# 18-Led7.net
KiCad netlist of a schematic drawn in Altium Designer
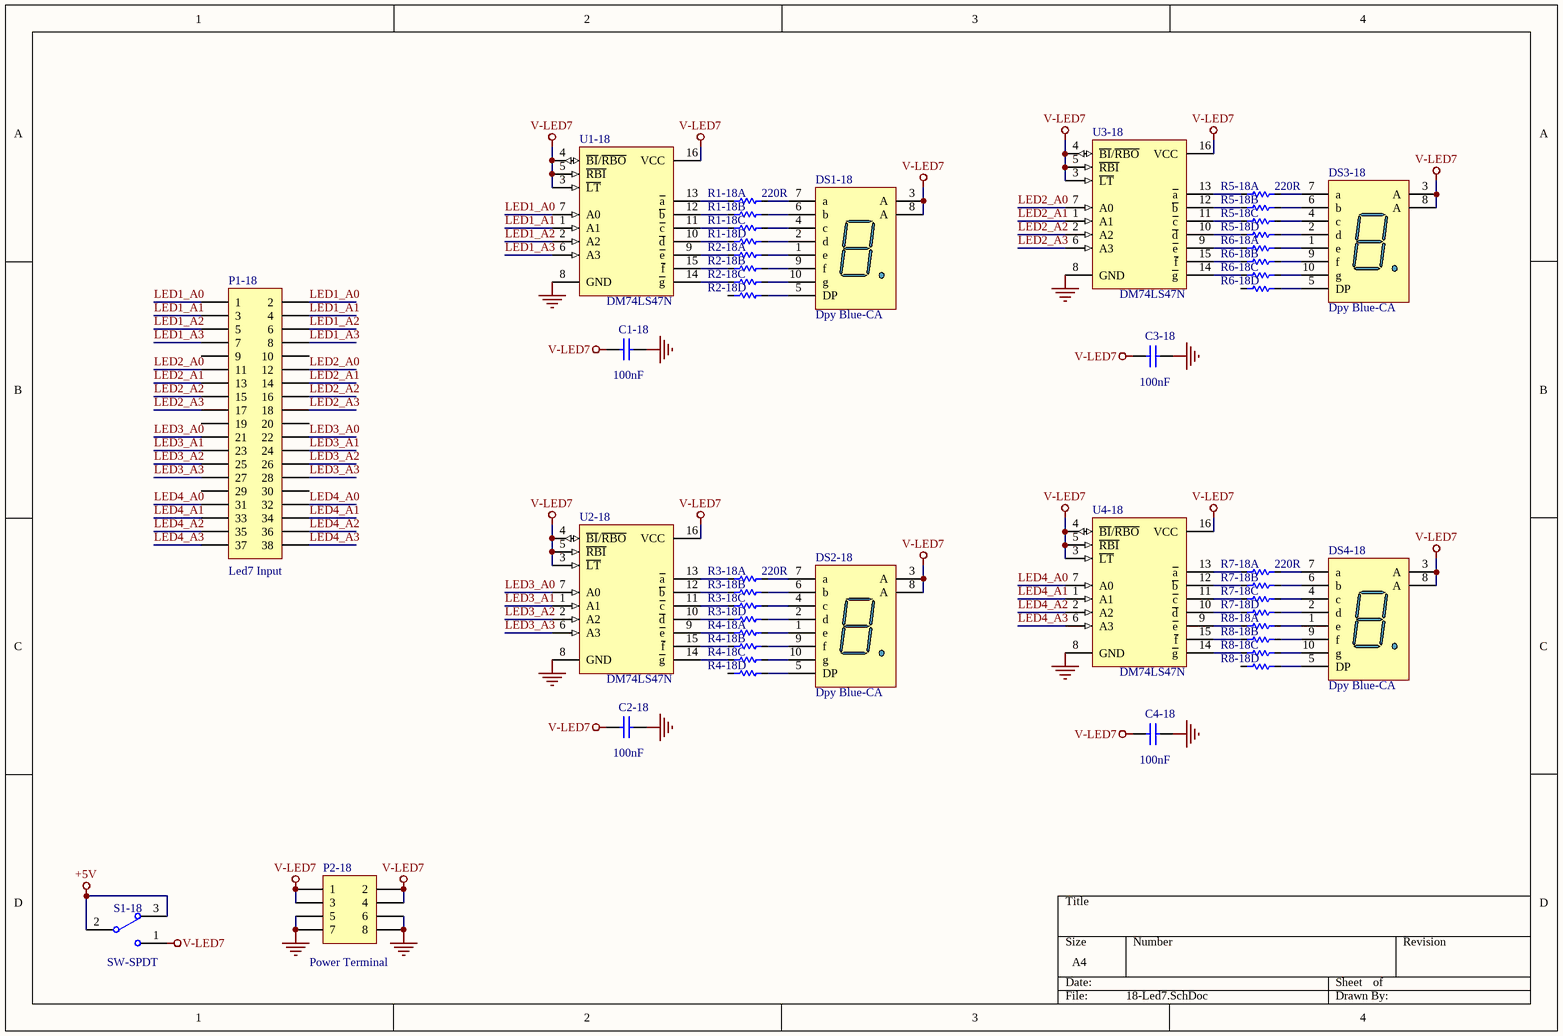
[diagram p0: 18-Led7.SchDoc]

(export (version "E")
  (design (tool "Eeschema 10.0.6"))
  (components
    (comp (ref "C1-18")
      (value "100nF")
      (footprint "c-0805")
      (description "Capacitor")
      (fields (field (name "Comment") "104") (field (name "PUBLISHER") "Altium Limited"))
      (libsource (lib "Miscellaneous Devices") (part "Cap"))
    )
    (comp (ref "C2-18")
      (value "100nF")
      (footprint "c-0805")
      (description "Capacitor")
      (fields (field (name "Comment") "104") (field (name "PUBLISHER") "Altium Limited"))
      (libsource (lib "Miscellaneous Devices") (part "Cap"))
    )
    (comp (ref "C3-18")
      (value "100nF")
      (footprint "c-0805")
      (description "Capacitor")
      (fields (field (name "Comment") "104") (field (name "PUBLISHER") "Altium Limited"))
      (libsource (lib "Miscellaneous Devices") (part "Cap"))
    )
    (comp (ref "C4-18")
      (value "100nF")
      (footprint "c-0805")
      (description "Capacitor")
      (fields (field (name "Comment") "104") (field (name "PUBLISHER") "Altium Limited"))
      (libsource (lib "Miscellaneous Devices") (part "Cap"))
    )
    (comp (ref "DS1-18")
      (value "Dpy Blue-CA")
      (footprint "LED7-0.56inch")
      (description "14.2 mm General Purpose Blue 7-Segment Display: CA, RH DP, Gray Surface")
      (fields (field (name "PUBLISHER") "Altium Limited"))
      (libsource (lib "Miscellaneous Devices") (part "Dpy Blue-CA"))
    )
    (comp (ref "DS2-18")
      (value "Dpy Blue-CA")
      (footprint "LED7-0.56inch")
      (description "14.2 mm General Purpose Blue 7-Segment Display: CA, RH DP, Gray Surface")
      (fields (field (name "PUBLISHER") "Altium Limited"))
      (libsource (lib "Miscellaneous Devices") (part "Dpy Blue-CA"))
    )
    (comp (ref "DS3-18")
      (value "Dpy Blue-CA")
      (footprint "LED7-0.56inch")
      (description "14.2 mm General Purpose Blue 7-Segment Display: CA, RH DP, Gray Surface")
      (fields (field (name "PUBLISHER") "Altium Limited"))
      (libsource (lib "Miscellaneous Devices") (part "Dpy Blue-CA"))
    )
    (comp (ref "DS4-18")
      (value "Dpy Blue-CA")
      (footprint "LED7-0.56inch")
      (description "14.2 mm General Purpose Blue 7-Segment Display: CA, RH DP, Gray Surface")
      (fields (field (name "PUBLISHER") "Altium Limited"))
      (libsource (lib "Miscellaneous Devices") (part "Dpy Blue-CA"))
    )
    (comp (ref "P1-18")
      (value "Led7 Input")
      (footprint "JP2.54-F-2x19A")
      (description "Header, 19-Pin, Dual row")
      (fields (field (name "Comment") "Header 19X2"))
      (libsource (lib "Miscellaneous Connectors") (part "Header 19X2"))
    )
    (comp (ref "P2-18")
      (value "Header 4X2")
      (footprint "JP2.54-F-2x04A")
      (description "Header, 4-Pin, Dual row")
      (fields (field (name "PUBLISHER") "Power Terminal"))
      (libsource (lib "Miscellaneous Connectors") (part "Header 4X2"))
    )
    (comp (ref "R1-18")
      (value "220R")
      (footprint "R-Array-0603-4")
      (description "RES ARRAY 4 RES 330 OHM 1206")
      (fields
        (field (name "DIGI-KEY PART NUMBER") "Y9331TR-ND")
        (field (name "MANUFACTURER") "Panasonic Electronic Components")
      )
      (libsource (lib "Dlib") (part "R-8P4R"))
    )
    (comp (ref "R2-18")
      (value "220R")
      (footprint "R-Array-0603-4")
      (description "RES ARRAY 4 RES 330 OHM 1206")
      (fields
        (field (name "DIGI-KEY PART NUMBER") "Y9331TR-ND")
        (field (name "MANUFACTURER") "Panasonic Electronic Components")
      )
      (libsource (lib "Dlib") (part "R-8P4R"))
    )
    (comp (ref "R3-18")
      (value "220R")
      (footprint "R-Array-0603-4")
      (description "RES ARRAY 4 RES 330 OHM 1206")
      (fields
        (field (name "DIGI-KEY PART NUMBER") "Y9331TR-ND")
        (field (name "MANUFACTURER") "Panasonic Electronic Components")
      )
      (libsource (lib "Dlib") (part "R-8P4R"))
    )
    (comp (ref "R4-18")
      (value "220R")
      (footprint "R-Array-0603-4")
      (description "RES ARRAY 4 RES 330 OHM 1206")
      (fields
        (field (name "DIGI-KEY PART NUMBER") "Y9331TR-ND")
        (field (name "MANUFACTURER") "Panasonic Electronic Components")
      )
      (libsource (lib "Dlib") (part "R-8P4R"))
    )
    (comp (ref "R5-18")
      (value "220R")
      (footprint "R-Array-0603-4")
      (description "RES ARRAY 4 RES 330 OHM 1206")
      (fields
        (field (name "DIGI-KEY PART NUMBER") "Y9331TR-ND")
        (field (name "MANUFACTURER") "Panasonic Electronic Components")
      )
      (libsource (lib "Dlib") (part "R-8P4R"))
    )
    (comp (ref "R6-18")
      (value "220R")
      (footprint "R-Array-0603-4")
      (description "RES ARRAY 4 RES 330 OHM 1206")
      (fields
        (field (name "DIGI-KEY PART NUMBER") "Y9331TR-ND")
        (field (name "MANUFACTURER") "Panasonic Electronic Components")
      )
      (libsource (lib "Dlib") (part "R-8P4R"))
    )
    (comp (ref "R7-18")
      (value "220R")
      (footprint "R-Array-0603-4")
      (description "RES ARRAY 4 RES 330 OHM 1206")
      (fields
        (field (name "DIGI-KEY PART NUMBER") "Y9331TR-ND")
        (field (name "MANUFACTURER") "Panasonic Electronic Components")
      )
      (libsource (lib "Dlib") (part "R-8P4R"))
    )
    (comp (ref "R8-18")
      (value "220R")
      (footprint "R-Array-0603-4")
      (description "RES ARRAY 4 RES 330 OHM 1206")
      (fields
        (field (name "DIGI-KEY PART NUMBER") "Y9331TR-ND")
        (field (name "MANUFACTURER") "Panasonic Electronic Components")
      )
      (libsource (lib "Dlib") (part "R-8P4R"))
    )
    (comp (ref "S1-18")
      (value "SW-SPDT")
      (footprint "SW-SLIDE-2P-2W")
      (description "SPDT Subminiature Toggle Switch, Right Angle Mounting, Vertical Actuation")
      (fields (field (name "PUBLISHER") "Altium Limited"))
      (libsource (lib "Miscellaneous Devices") (part "SW-SPDT"))
    )
    (comp (ref "U1-18")
      (value "DM74LS47N")
      (footprint "SK-DIP16-300")
      (description "BCD to 7-Segment Decoder/Driver with Open-Collector Output")
      (fields (field (name "PUBLISHER") "Altium Limited"))
      (libsource (lib "FSC Interface Display Driver") (part "DM74LS47N"))
    )
    (comp (ref "U2-18")
      (value "DM74LS47N")
      (footprint "SK-DIP16-300")
      (description "BCD to 7-Segment Decoder/Driver with Open-Collector Output")
      (fields (field (name "PUBLISHER") "Altium Limited"))
      (libsource (lib "FSC Interface Display Driver") (part "DM74LS47N"))
    )
    (comp (ref "U3-18")
      (value "DM74LS47N")
      (footprint "SK-DIP16-300")
      (description "BCD to 7-Segment Decoder/Driver with Open-Collector Output")
      (fields (field (name "PUBLISHER") "Altium Limited"))
      (libsource (lib "FSC Interface Display Driver") (part "DM74LS47N"))
    )
    (comp (ref "U4-18")
      (value "DM74LS47N")
      (footprint "SK-DIP16-300")
      (description "BCD to 7-Segment Decoder/Driver with Open-Collector Output")
      (fields (field (name "PUBLISHER") "Altium Limited"))
      (libsource (lib "FSC Interface Display Driver") (part "DM74LS47N"))
    )
  )
  (nets
    (net (code "1") (name "+5V") (class "Default")
      (node (ref "S1-18") (pin "2") (pinfunction "2_2") (pintype "passive"))
      (node (ref "S1-18") (pin "3") (pinfunction "3_3") (pintype "passive"))
    )
    (net (code "2") (name "/LED1_A0") (class "Default")
      (node (ref "P1-18") (pin "1") (pinfunction "1_1") (pintype "passive"))
      (node (ref "P1-18") (pin "2") (pinfunction "2_2") (pintype "passive"))
      (node (ref "U1-18") (pin "7") (pinfunction "A0_7") (pintype "input"))
    )
    (net (code "3") (name "/LED1_A1") (class "Default")
      (node (ref "P1-18") (pin "3") (pinfunction "3_3") (pintype "passive"))
      (node (ref "P1-18") (pin "4") (pinfunction "4_4") (pintype "passive"))
      (node (ref "U1-18") (pin "1") (pinfunction "A1_1") (pintype "input"))
    )
    (net (code "4") (name "/LED1_A2") (class "Default")
      (node (ref "P1-18") (pin "5") (pinfunction "5_5") (pintype "passive"))
      (node (ref "P1-18") (pin "6") (pinfunction "6_6") (pintype "passive"))
      (node (ref "U1-18") (pin "2") (pinfunction "A2_2") (pintype "input"))
    )
    (net (code "5") (name "/LED1_A3") (class "Default")
      (node (ref "P1-18") (pin "7") (pinfunction "7_7") (pintype "passive"))
      (node (ref "P1-18") (pin "8") (pinfunction "8_8") (pintype "passive"))
      (node (ref "U1-18") (pin "6") (pinfunction "A3_6") (pintype "input"))
    )
    (net (code "6") (name "/LED2_A0") (class "Default")
      (node (ref "P1-18") (pin "11") (pinfunction "11_11") (pintype "passive"))
      (node (ref "P1-18") (pin "12") (pinfunction "12_12") (pintype "passive"))
      (node (ref "U3-18") (pin "7") (pinfunction "A0_7") (pintype "input"))
    )
    (net (code "7") (name "/LED2_A1") (class "Default")
      (node (ref "P1-18") (pin "13") (pinfunction "13_13") (pintype "passive"))
      (node (ref "P1-18") (pin "14") (pinfunction "14_14") (pintype "passive"))
      (node (ref "U3-18") (pin "1") (pinfunction "A1_1") (pintype "input"))
    )
    (net (code "8") (name "/LED2_A2") (class "Default")
      (node (ref "P1-18") (pin "15") (pinfunction "15_15") (pintype "passive"))
      (node (ref "P1-18") (pin "16") (pinfunction "16_16") (pintype "passive"))
      (node (ref "U3-18") (pin "2") (pinfunction "A2_2") (pintype "input"))
    )
    (net (code "9") (name "/LED2_A3") (class "Default")
      (node (ref "P1-18") (pin "17") (pinfunction "17_17") (pintype "passive"))
      (node (ref "P1-18") (pin "18") (pinfunction "18_18") (pintype "passive"))
      (node (ref "U3-18") (pin "6") (pinfunction "A3_6") (pintype "input"))
    )
    (net (code "10") (name "/LED3_A0") (class "Default")
      (node (ref "P1-18") (pin "21") (pinfunction "21_21") (pintype "passive"))
      (node (ref "P1-18") (pin "22") (pinfunction "22_22") (pintype "passive"))
      (node (ref "U2-18") (pin "7") (pinfunction "A0_7") (pintype "input"))
    )
    (net (code "11") (name "/LED3_A1") (class "Default")
      (node (ref "P1-18") (pin "23") (pinfunction "23_23") (pintype "passive"))
      (node (ref "P1-18") (pin "24") (pinfunction "24_24") (pintype "passive"))
      (node (ref "U2-18") (pin "1") (pinfunction "A1_1") (pintype "input"))
    )
    (net (code "12") (name "/LED3_A2") (class "Default")
      (node (ref "P1-18") (pin "25") (pinfunction "25_25") (pintype "passive"))
      (node (ref "P1-18") (pin "26") (pinfunction "26_26") (pintype "passive"))
      (node (ref "U2-18") (pin "2") (pinfunction "A2_2") (pintype "input"))
    )
    (net (code "13") (name "/LED3_A3") (class "Default")
      (node (ref "P1-18") (pin "27") (pinfunction "27_27") (pintype "passive"))
      (node (ref "P1-18") (pin "28") (pinfunction "28_28") (pintype "passive"))
      (node (ref "U2-18") (pin "6") (pinfunction "A3_6") (pintype "input"))
    )
    (net (code "14") (name "/LED4_A0") (class "Default")
      (node (ref "P1-18") (pin "31") (pinfunction "31_31") (pintype "passive"))
      (node (ref "P1-18") (pin "32") (pinfunction "32_32") (pintype "passive"))
      (node (ref "U4-18") (pin "7") (pinfunction "A0_7") (pintype "input"))
    )
    (net (code "15") (name "/LED4_A1") (class "Default")
      (node (ref "P1-18") (pin "33") (pinfunction "33_33") (pintype "passive"))
      (node (ref "P1-18") (pin "34") (pinfunction "34_34") (pintype "passive"))
      (node (ref "U4-18") (pin "1") (pinfunction "A1_1") (pintype "input"))
    )
    (net (code "16") (name "/LED4_A2") (class "Default")
      (node (ref "P1-18") (pin "35") (pinfunction "35_35") (pintype "passive"))
      (node (ref "P1-18") (pin "36") (pinfunction "36_36") (pintype "passive"))
      (node (ref "U4-18") (pin "2") (pinfunction "A2_2") (pintype "input"))
    )
    (net (code "17") (name "/LED4_A3") (class "Default")
      (node (ref "P1-18") (pin "37") (pinfunction "37_37") (pintype "passive"))
      (node (ref "P1-18") (pin "38") (pinfunction "38_38") (pintype "passive"))
      (node (ref "U4-18") (pin "6") (pinfunction "A3_6") (pintype "input"))
    )
    (net (code "18") (name "GND") (class "Default")
      (node (ref "C1-18") (pin "2") (pinfunction "2_2") (pintype "passive"))
      (node (ref "C2-18") (pin "2") (pinfunction "2_2") (pintype "passive"))
      (node (ref "C3-18") (pin "2") (pinfunction "2_2") (pintype "passive"))
      (node (ref "C4-18") (pin "2") (pinfunction "2_2") (pintype "passive"))
      (node (ref "P2-18") (pin "5") (pinfunction "5_5") (pintype "passive"))
      (node (ref "P2-18") (pin "6") (pinfunction "6_6") (pintype "passive"))
      (node (ref "P2-18") (pin "7") (pinfunction "7_7") (pintype "passive"))
      (node (ref "P2-18") (pin "8") (pinfunction "8_8") (pintype "passive"))
      (node (ref "U1-18") (pin "8") (pinfunction "GND_8") (pintype "power_in"))
      (node (ref "U2-18") (pin "8") (pinfunction "GND_8") (pintype "power_in"))
      (node (ref "U3-18") (pin "8") (pinfunction "GND_8") (pintype "power_in"))
      (node (ref "U4-18") (pin "8") (pinfunction "GND_8") (pintype "power_in"))
    )
    (net (code "19") (name "Net-(DS1-18-DP)") (class "Default")
      (node (ref "DS1-18") (pin "5") (pinfunction "DP_5") (pintype "passive"))
      (node (ref "R2-18") (pin "8") (pinfunction "2_8") (pintype "passive"))
    )
    (net (code "20") (name "Net-(DS1-18-a)") (class "Default")
      (node (ref "DS1-18") (pin "7") (pinfunction "a_7") (pintype "passive"))
      (node (ref "R1-18") (pin "2") (pinfunction "2_2") (pintype "passive"))
    )
    (net (code "21") (name "Net-(DS1-18-b)") (class "Default")
      (node (ref "DS1-18") (pin "6") (pinfunction "b_6") (pintype "passive"))
      (node (ref "R1-18") (pin "4") (pinfunction "2_4") (pintype "passive"))
    )
    (net (code "22") (name "Net-(DS1-18-c)") (class "Default")
      (node (ref "DS1-18") (pin "4") (pinfunction "c_4") (pintype "passive"))
      (node (ref "R1-18") (pin "6") (pinfunction "2_6") (pintype "passive"))
    )
    (net (code "23") (name "Net-(DS1-18-d)") (class "Default")
      (node (ref "DS1-18") (pin "2") (pinfunction "d_2") (pintype "passive"))
      (node (ref "R1-18") (pin "8") (pinfunction "2_8") (pintype "passive"))
    )
    (net (code "24") (name "Net-(DS1-18-e)") (class "Default")
      (node (ref "DS1-18") (pin "1") (pinfunction "e_1") (pintype "passive"))
      (node (ref "R2-18") (pin "2") (pinfunction "2_2") (pintype "passive"))
    )
    (net (code "25") (name "Net-(DS1-18-f)") (class "Default")
      (node (ref "DS1-18") (pin "9") (pinfunction "f_9") (pintype "passive"))
      (node (ref "R2-18") (pin "4") (pinfunction "2_4") (pintype "passive"))
    )
    (net (code "26") (name "Net-(DS1-18-g)") (class "Default")
      (node (ref "DS1-18") (pin "10") (pinfunction "g_10") (pintype "passive"))
      (node (ref "R2-18") (pin "6") (pinfunction "2_6") (pintype "passive"))
    )
    (net (code "27") (name "Net-(DS2-18-DP)") (class "Default")
      (node (ref "DS2-18") (pin "5") (pinfunction "DP_5") (pintype "passive"))
      (node (ref "R4-18") (pin "8") (pinfunction "2_8") (pintype "passive"))
    )
    (net (code "28") (name "Net-(DS2-18-a)") (class "Default")
      (node (ref "DS2-18") (pin "7") (pinfunction "a_7") (pintype "passive"))
      (node (ref "R3-18") (pin "2") (pinfunction "2_2") (pintype "passive"))
    )
    (net (code "29") (name "Net-(DS2-18-b)") (class "Default")
      (node (ref "DS2-18") (pin "6") (pinfunction "b_6") (pintype "passive"))
      (node (ref "R3-18") (pin "4") (pinfunction "2_4") (pintype "passive"))
    )
    (net (code "30") (name "Net-(DS2-18-c)") (class "Default")
      (node (ref "DS2-18") (pin "4") (pinfunction "c_4") (pintype "passive"))
      (node (ref "R3-18") (pin "6") (pinfunction "2_6") (pintype "passive"))
    )
    (net (code "31") (name "Net-(DS2-18-d)") (class "Default")
      (node (ref "DS2-18") (pin "2") (pinfunction "d_2") (pintype "passive"))
      (node (ref "R3-18") (pin "8") (pinfunction "2_8") (pintype "passive"))
    )
    (net (code "32") (name "Net-(DS2-18-e)") (class "Default")
      (node (ref "DS2-18") (pin "1") (pinfunction "e_1") (pintype "passive"))
      (node (ref "R4-18") (pin "2") (pinfunction "2_2") (pintype "passive"))
    )
    (net (code "33") (name "Net-(DS2-18-f)") (class "Default")
      (node (ref "DS2-18") (pin "9") (pinfunction "f_9") (pintype "passive"))
      (node (ref "R4-18") (pin "4") (pinfunction "2_4") (pintype "passive"))
    )
    (net (code "34") (name "Net-(DS2-18-g)") (class "Default")
      (node (ref "DS2-18") (pin "10") (pinfunction "g_10") (pintype "passive"))
      (node (ref "R4-18") (pin "6") (pinfunction "2_6") (pintype "passive"))
    )
    (net (code "35") (name "Net-(DS3-18-DP)") (class "Default")
      (node (ref "DS3-18") (pin "5") (pinfunction "DP_5") (pintype "passive"))
      (node (ref "R6-18") (pin "8") (pinfunction "2_8") (pintype "passive"))
    )
    (net (code "36") (name "Net-(DS3-18-a)") (class "Default")
      (node (ref "DS3-18") (pin "7") (pinfunction "a_7") (pintype "passive"))
      (node (ref "R5-18") (pin "2") (pinfunction "2_2") (pintype "passive"))
    )
    (net (code "37") (name "Net-(DS3-18-b)") (class "Default")
      (node (ref "DS3-18") (pin "6") (pinfunction "b_6") (pintype "passive"))
      (node (ref "R5-18") (pin "4") (pinfunction "2_4") (pintype "passive"))
    )
    (net (code "38") (name "Net-(DS3-18-c)") (class "Default")
      (node (ref "DS3-18") (pin "4") (pinfunction "c_4") (pintype "passive"))
      (node (ref "R5-18") (pin "6") (pinfunction "2_6") (pintype "passive"))
    )
    (net (code "39") (name "Net-(DS3-18-d)") (class "Default")
      (node (ref "DS3-18") (pin "2") (pinfunction "d_2") (pintype "passive"))
      (node (ref "R5-18") (pin "8") (pinfunction "2_8") (pintype "passive"))
    )
    (net (code "40") (name "Net-(DS3-18-e)") (class "Default")
      (node (ref "DS3-18") (pin "1") (pinfunction "e_1") (pintype "passive"))
      (node (ref "R6-18") (pin "2") (pinfunction "2_2") (pintype "passive"))
    )
    (net (code "41") (name "Net-(DS3-18-f)") (class "Default")
      (node (ref "DS3-18") (pin "9") (pinfunction "f_9") (pintype "passive"))
      (node (ref "R6-18") (pin "4") (pinfunction "2_4") (pintype "passive"))
    )
    (net (code "42") (name "Net-(DS3-18-g)") (class "Default")
      (node (ref "DS3-18") (pin "10") (pinfunction "g_10") (pintype "passive"))
      (node (ref "R6-18") (pin "6") (pinfunction "2_6") (pintype "passive"))
    )
    (net (code "43") (name "Net-(DS4-18-DP)") (class "Default")
      (node (ref "DS4-18") (pin "5") (pinfunction "DP_5") (pintype "passive"))
      (node (ref "R8-18") (pin "8") (pinfunction "2_8") (pintype "passive"))
    )
    (net (code "44") (name "Net-(DS4-18-a)") (class "Default")
      (node (ref "DS4-18") (pin "7") (pinfunction "a_7") (pintype "passive"))
      (node (ref "R7-18") (pin "2") (pinfunction "2_2") (pintype "passive"))
    )
    (net (code "45") (name "Net-(DS4-18-b)") (class "Default")
      (node (ref "DS4-18") (pin "6") (pinfunction "b_6") (pintype "passive"))
      (node (ref "R7-18") (pin "4") (pinfunction "2_4") (pintype "passive"))
    )
    (net (code "46") (name "Net-(DS4-18-c)") (class "Default")
      (node (ref "DS4-18") (pin "4") (pinfunction "c_4") (pintype "passive"))
      (node (ref "R7-18") (pin "6") (pinfunction "2_6") (pintype "passive"))
    )
    (net (code "47") (name "Net-(DS4-18-d)") (class "Default")
      (node (ref "DS4-18") (pin "2") (pinfunction "d_2") (pintype "passive"))
      (node (ref "R7-18") (pin "8") (pinfunction "2_8") (pintype "passive"))
    )
    (net (code "48") (name "Net-(DS4-18-e)") (class "Default")
      (node (ref "DS4-18") (pin "1") (pinfunction "e_1") (pintype "passive"))
      (node (ref "R8-18") (pin "2") (pinfunction "2_2") (pintype "passive"))
    )
    (net (code "49") (name "Net-(DS4-18-f)") (class "Default")
      (node (ref "DS4-18") (pin "9") (pinfunction "f_9") (pintype "passive"))
      (node (ref "R8-18") (pin "4") (pinfunction "2_4") (pintype "passive"))
    )
    (net (code "50") (name "Net-(DS4-18-g)") (class "Default")
      (node (ref "DS4-18") (pin "10") (pinfunction "g_10") (pintype "passive"))
      (node (ref "R8-18") (pin "6") (pinfunction "2_6") (pintype "passive"))
    )
    (net (code "51") (name "Net-(R1-18B-1)") (class "Default")
      (node (ref "R1-18") (pin "3") (pinfunction "1_3") (pintype "passive"))
      (node (ref "U1-18") (pin "12") (pinfunction "~{b}_12") (pintype "open_collector"))
    )
    (net (code "52") (name "Net-(R1-18C-1)") (class "Default")
      (node (ref "R1-18") (pin "5") (pinfunction "1_5") (pintype "passive"))
      (node (ref "U1-18") (pin "11") (pinfunction "~{c}_11") (pintype "open_collector"))
    )
    (net (code "53") (name "Net-(R1-18D-1)") (class "Default")
      (node (ref "R1-18") (pin "7") (pinfunction "1_7") (pintype "passive"))
      (node (ref "U1-18") (pin "10") (pinfunction "~{d}_10") (pintype "open_collector"))
    )
    (net (code "54") (name "Net-(R2-18B-1)") (class "Default")
      (node (ref "R2-18") (pin "3") (pinfunction "1_3") (pintype "passive"))
      (node (ref "U1-18") (pin "15") (pinfunction "~{f}_15") (pintype "open_collector"))
    )
    (net (code "55") (name "Net-(R2-18C-1)") (class "Default")
      (node (ref "R2-18") (pin "5") (pinfunction "1_5") (pintype "passive"))
      (node (ref "U1-18") (pin "14") (pinfunction "~{g}_14") (pintype "open_collector"))
    )
    (net (code "56") (name "Net-(R3-18B-1)") (class "Default")
      (node (ref "R3-18") (pin "3") (pinfunction "1_3") (pintype "passive"))
      (node (ref "U2-18") (pin "12") (pinfunction "~{b}_12") (pintype "open_collector"))
    )
    (net (code "57") (name "Net-(R3-18C-1)") (class "Default")
      (node (ref "R3-18") (pin "5") (pinfunction "1_5") (pintype "passive"))
      (node (ref "U2-18") (pin "11") (pinfunction "~{c}_11") (pintype "open_collector"))
    )
    (net (code "58") (name "Net-(R3-18D-1)") (class "Default")
      (node (ref "R3-18") (pin "7") (pinfunction "1_7") (pintype "passive"))
      (node (ref "U2-18") (pin "10") (pinfunction "~{d}_10") (pintype "open_collector"))
    )
    (net (code "59") (name "Net-(R4-18B-1)") (class "Default")
      (node (ref "R4-18") (pin "3") (pinfunction "1_3") (pintype "passive"))
      (node (ref "U2-18") (pin "15") (pinfunction "~{f}_15") (pintype "open_collector"))
    )
    (net (code "60") (name "Net-(R4-18C-1)") (class "Default")
      (node (ref "R4-18") (pin "5") (pinfunction "1_5") (pintype "passive"))
      (node (ref "U2-18") (pin "14") (pinfunction "~{g}_14") (pintype "open_collector"))
    )
    (net (code "61") (name "Net-(R5-18B-1)") (class "Default")
      (node (ref "R5-18") (pin "3") (pinfunction "1_3") (pintype "passive"))
      (node (ref "U3-18") (pin "12") (pinfunction "~{b}_12") (pintype "open_collector"))
    )
    (net (code "62") (name "Net-(R5-18C-1)") (class "Default")
      (node (ref "R5-18") (pin "5") (pinfunction "1_5") (pintype "passive"))
      (node (ref "U3-18") (pin "11") (pinfunction "~{c}_11") (pintype "open_collector"))
    )
    (net (code "63") (name "Net-(R5-18D-1)") (class "Default")
      (node (ref "R5-18") (pin "7") (pinfunction "1_7") (pintype "passive"))
      (node (ref "U3-18") (pin "10") (pinfunction "~{d}_10") (pintype "open_collector"))
    )
    (net (code "64") (name "Net-(R6-18B-1)") (class "Default")
      (node (ref "R6-18") (pin "3") (pinfunction "1_3") (pintype "passive"))
      (node (ref "U3-18") (pin "15") (pinfunction "~{f}_15") (pintype "open_collector"))
    )
    (net (code "65") (name "Net-(R6-18C-1)") (class "Default")
      (node (ref "R6-18") (pin "5") (pinfunction "1_5") (pintype "passive"))
      (node (ref "U3-18") (pin "14") (pinfunction "~{g}_14") (pintype "open_collector"))
    )
    (net (code "66") (name "Net-(R7-18B-1)") (class "Default")
      (node (ref "R7-18") (pin "3") (pinfunction "1_3") (pintype "passive"))
      (node (ref "U4-18") (pin "12") (pinfunction "~{b}_12") (pintype "open_collector"))
    )
    (net (code "67") (name "Net-(R7-18C-1)") (class "Default")
      (node (ref "R7-18") (pin "5") (pinfunction "1_5") (pintype "passive"))
      (node (ref "U4-18") (pin "11") (pinfunction "~{c}_11") (pintype "open_collector"))
    )
    (net (code "68") (name "Net-(R7-18D-1)") (class "Default")
      (node (ref "R7-18") (pin "7") (pinfunction "1_7") (pintype "passive"))
      (node (ref "U4-18") (pin "10") (pinfunction "~{d}_10") (pintype "open_collector"))
    )
    (net (code "69") (name "Net-(R8-18B-1)") (class "Default")
      (node (ref "R8-18") (pin "3") (pinfunction "1_3") (pintype "passive"))
      (node (ref "U4-18") (pin "15") (pinfunction "~{f}_15") (pintype "open_collector"))
    )
    (net (code "70") (name "Net-(R8-18C-1)") (class "Default")
      (node (ref "R8-18") (pin "5") (pinfunction "1_5") (pintype "passive"))
      (node (ref "U4-18") (pin "14") (pinfunction "~{g}_14") (pintype "open_collector"))
    )
    (net (code "71") (name "Net-(U1-18-~{a})") (class "Default")
      (node (ref "R1-18") (pin "1") (pinfunction "1_1") (pintype "passive"))
      (node (ref "U1-18") (pin "13") (pinfunction "~{a}_13") (pintype "open_collector"))
    )
    (net (code "72") (name "Net-(U1-18-~{e})") (class "Default")
      (node (ref "R2-18") (pin "1") (pinfunction "1_1") (pintype "passive"))
      (node (ref "U1-18") (pin "9") (pinfunction "~{e}_9") (pintype "open_collector"))
    )
    (net (code "73") (name "Net-(U2-18-~{a})") (class "Default")
      (node (ref "R3-18") (pin "1") (pinfunction "1_1") (pintype "passive"))
      (node (ref "U2-18") (pin "13") (pinfunction "~{a}_13") (pintype "open_collector"))
    )
    (net (code "74") (name "Net-(U2-18-~{e})") (class "Default")
      (node (ref "R4-18") (pin "1") (pinfunction "1_1") (pintype "passive"))
      (node (ref "U2-18") (pin "9") (pinfunction "~{e}_9") (pintype "open_collector"))
    )
    (net (code "75") (name "Net-(U3-18-~{a})") (class "Default")
      (node (ref "R5-18") (pin "1") (pinfunction "1_1") (pintype "passive"))
      (node (ref "U3-18") (pin "13") (pinfunction "~{a}_13") (pintype "open_collector"))
    )
    (net (code "76") (name "Net-(U3-18-~{e})") (class "Default")
      (node (ref "R6-18") (pin "1") (pinfunction "1_1") (pintype "passive"))
      (node (ref "U3-18") (pin "9") (pinfunction "~{e}_9") (pintype "open_collector"))
    )
    (net (code "77") (name "Net-(U4-18-~{a})") (class "Default")
      (node (ref "R7-18") (pin "1") (pinfunction "1_1") (pintype "passive"))
      (node (ref "U4-18") (pin "13") (pinfunction "~{a}_13") (pintype "open_collector"))
    )
    (net (code "78") (name "Net-(U4-18-~{e})") (class "Default")
      (node (ref "R8-18") (pin "1") (pinfunction "1_1") (pintype "passive"))
      (node (ref "U4-18") (pin "9") (pinfunction "~{e}_9") (pintype "open_collector"))
    )
    (net (code "79") (name "V-LED7") (class "Default")
      (node (ref "C1-18") (pin "1") (pinfunction "1_1") (pintype "passive"))
      (node (ref "C2-18") (pin "1") (pinfunction "1_1") (pintype "passive"))
      (node (ref "C3-18") (pin "1") (pinfunction "1_1") (pintype "passive"))
      (node (ref "C4-18") (pin "1") (pinfunction "1_1") (pintype "passive"))
      (node (ref "DS1-18") (pin "3") (pinfunction "A_3") (pintype "passive"))
      (node (ref "DS1-18") (pin "8") (pinfunction "A_8") (pintype "passive"))
      (node (ref "DS2-18") (pin "3") (pinfunction "A_3") (pintype "passive"))
      (node (ref "DS2-18") (pin "8") (pinfunction "A_8") (pintype "passive"))
      (node (ref "DS3-18") (pin "3") (pinfunction "A_3") (pintype "passive"))
      (node (ref "DS3-18") (pin "8") (pinfunction "A_8") (pintype "passive"))
      (node (ref "DS4-18") (pin "3") (pinfunction "A_3") (pintype "passive"))
      (node (ref "DS4-18") (pin "8") (pinfunction "A_8") (pintype "passive"))
      (node (ref "P2-18") (pin "1") (pinfunction "1_1") (pintype "passive"))
      (node (ref "P2-18") (pin "2") (pinfunction "2_2") (pintype "passive"))
      (node (ref "P2-18") (pin "3") (pinfunction "3_3") (pintype "passive"))
      (node (ref "P2-18") (pin "4") (pinfunction "4_4") (pintype "passive"))
      (node (ref "S1-18") (pin "1") (pinfunction "1_1") (pintype "passive"))
      (node (ref "U1-18") (pin "16") (pinfunction "VCC_16") (pintype "power_in"))
      (node (ref "U1-18") (pin "3") (pinfunction "~{LT}_3") (pintype "input"))
      (node (ref "U1-18") (pin "4") (pinfunction "~{BI}/~{RBO}_4") (pintype "bidirectional"))
      (node (ref "U1-18") (pin "5") (pinfunction "~{RBI}_5") (pintype "input"))
      (node (ref "U2-18") (pin "16") (pinfunction "VCC_16") (pintype "power_in"))
      (node (ref "U2-18") (pin "3") (pinfunction "~{LT}_3") (pintype "input"))
      (node (ref "U2-18") (pin "4") (pinfunction "~{BI}/~{RBO}_4") (pintype "bidirectional"))
      (node (ref "U2-18") (pin "5") (pinfunction "~{RBI}_5") (pintype "input"))
      (node (ref "U3-18") (pin "16") (pinfunction "VCC_16") (pintype "power_in"))
      (node (ref "U3-18") (pin "3") (pinfunction "~{LT}_3") (pintype "input"))
      (node (ref "U3-18") (pin "4") (pinfunction "~{BI}/~{RBO}_4") (pintype "bidirectional"))
      (node (ref "U3-18") (pin "5") (pinfunction "~{RBI}_5") (pintype "input"))
      (node (ref "U4-18") (pin "16") (pinfunction "VCC_16") (pintype "power_in"))
      (node (ref "U4-18") (pin "3") (pinfunction "~{LT}_3") (pintype "input"))
      (node (ref "U4-18") (pin "4") (pinfunction "~{BI}/~{RBO}_4") (pintype "bidirectional"))
      (node (ref "U4-18") (pin "5") (pinfunction "~{RBI}_5") (pintype "input"))
    )
    (net (code "80") (name "unconnected-(P1-18-Pad9)") (class "Default")
      (node (ref "P1-18") (pin "9") (pinfunction "9_9") (pintype "passive"))
    )
    (net (code "81") (name "unconnected-(P1-18-Pad10)") (class "Default")
      (node (ref "P1-18") (pin "10") (pinfunction "10_10") (pintype "passive"))
    )
    (net (code "82") (name "unconnected-(P1-18-Pad19)") (class "Default")
      (node (ref "P1-18") (pin "19") (pinfunction "19_19") (pintype "passive"))
    )
    (net (code "83") (name "unconnected-(P1-18-Pad20)") (class "Default")
      (node (ref "P1-18") (pin "20") (pinfunction "20_20") (pintype "passive"))
    )
    (net (code "84") (name "unconnected-(P1-18-Pad29)") (class "Default")
      (node (ref "P1-18") (pin "29") (pinfunction "29_29") (pintype "passive"))
    )
    (net (code "85") (name "unconnected-(P1-18-Pad30)") (class "Default")
      (node (ref "P1-18") (pin "30") (pinfunction "30_30") (pintype "passive"))
    )
    (net (code "86") (name "unconnected-(R2-18D-1-Pad7)") (class "Default")
      (node (ref "R2-18") (pin "7") (pinfunction "1_7") (pintype "passive"))
    )
    (net (code "87") (name "unconnected-(R4-18D-1-Pad7)") (class "Default")
      (node (ref "R4-18") (pin "7") (pinfunction "1_7") (pintype "passive"))
    )
    (net (code "88") (name "unconnected-(R6-18D-1-Pad7)") (class "Default")
      (node (ref "R6-18") (pin "7") (pinfunction "1_7") (pintype "passive"))
    )
    (net (code "89") (name "unconnected-(R8-18D-1-Pad7)") (class "Default")
      (node (ref "R8-18") (pin "7") (pinfunction "1_7") (pintype "passive"))
    )
  )
)
